# Sheet2.net
KiCad netlist of a schematic drawn in Altium Designer
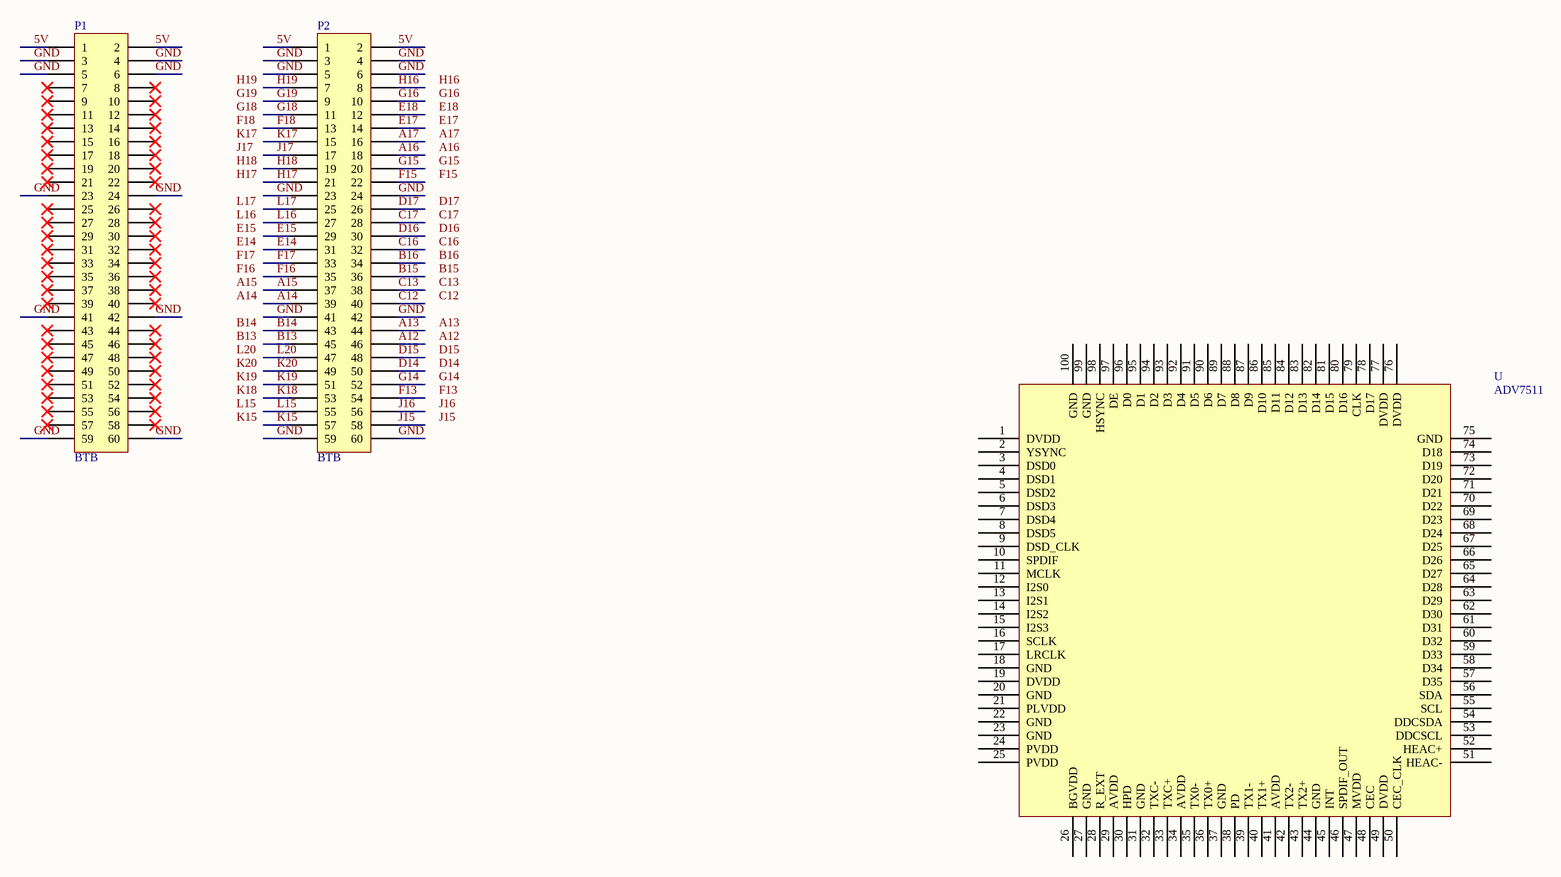
[diagram p0: Sheet2.SchDoc]

(export (version "E")
  (design (tool "Eeschema 10.0.6"))
  (components
    (comp (ref "P1")
      (value "BTB")
      (footprint "BTBCON_0.8mm_60P")
      (description "Header, 30-Pin, Dual row")
      (fields (field (name "PUBLISHER") "Altium Limited"))
      (libsource (lib "Miscellaneous Connectors") (part "Header 30X2"))
    )
    (comp (ref "P2")
      (value "BTB")
      (footprint "BTBCON_0.8mm_60P")
      (description "Header, 30-Pin, Dual row")
      (fields (field (name "PUBLISHER") "Altium Limited"))
      (libsource (lib "Miscellaneous Connectors") (part "Header 30X2"))
    )
    (comp (ref "U") (value "ADV7511") (libsource (lib "ADV7511") (part "ADV7511")))
  )
  (nets
    (net (code "1") (name "/5V") (class "Default")
      (node (ref "P1") (pin "1") (pinfunction "1_1") (pintype "passive"))
      (node (ref "P1") (pin "2") (pinfunction "2_2") (pintype "passive"))
      (node (ref "P2") (pin "1") (pinfunction "1_1") (pintype "passive"))
      (node (ref "P2") (pin "2") (pinfunction "2_2") (pintype "passive"))
    )
    (net (code "2") (name "/A12") (class "Default")
      (node (ref "P2") (pin "46") (pinfunction "46_46") (pintype "passive"))
    )
    (net (code "3") (name "/A13") (class "Default")
      (node (ref "P2") (pin "44") (pinfunction "44_44") (pintype "passive"))
    )
    (net (code "4") (name "/A14") (class "Default")
      (node (ref "P2") (pin "39") (pinfunction "39_39") (pintype "passive"))
    )
    (net (code "5") (name "/A15") (class "Default")
      (node (ref "P2") (pin "37") (pinfunction "37_37") (pintype "passive"))
    )
    (net (code "6") (name "/A16") (class "Default")
      (node (ref "P2") (pin "18") (pinfunction "18_18") (pintype "passive"))
    )
    (net (code "7") (name "/A17") (class "Default")
      (node (ref "P2") (pin "16") (pinfunction "16_16") (pintype "passive"))
    )
    (net (code "8") (name "/B13") (class "Default")
      (node (ref "P2") (pin "45") (pinfunction "45_45") (pintype "passive"))
    )
    (net (code "9") (name "/B14") (class "Default")
      (node (ref "P2") (pin "43") (pinfunction "43_43") (pintype "passive"))
    )
    (net (code "10") (name "/B15") (class "Default")
      (node (ref "P2") (pin "36") (pinfunction "36_36") (pintype "passive"))
    )
    (net (code "11") (name "/B16") (class "Default")
      (node (ref "P2") (pin "34") (pinfunction "34_34") (pintype "passive"))
    )
    (net (code "12") (name "/C12") (class "Default")
      (node (ref "P2") (pin "40") (pinfunction "40_40") (pintype "passive"))
    )
    (net (code "13") (name "/C13") (class "Default")
      (node (ref "P2") (pin "38") (pinfunction "38_38") (pintype "passive"))
    )
    (net (code "14") (name "/C16") (class "Default")
      (node (ref "P2") (pin "32") (pinfunction "32_32") (pintype "passive"))
    )
    (net (code "15") (name "/C17") (class "Default")
      (node (ref "P2") (pin "28") (pinfunction "28_28") (pintype "passive"))
    )
    (net (code "16") (name "/D14") (class "Default")
      (node (ref "P2") (pin "50") (pinfunction "50_50") (pintype "passive"))
    )
    (net (code "17") (name "/D15") (class "Default")
      (node (ref "P2") (pin "48") (pinfunction "48_48") (pintype "passive"))
    )
    (net (code "18") (name "/D16") (class "Default")
      (node (ref "P2") (pin "30") (pinfunction "30_30") (pintype "passive"))
    )
    (net (code "19") (name "/D17") (class "Default")
      (node (ref "P2") (pin "26") (pinfunction "26_26") (pintype "passive"))
    )
    (net (code "20") (name "/E14") (class "Default")
      (node (ref "P2") (pin "31") (pinfunction "31_31") (pintype "passive"))
    )
    (net (code "21") (name "/E15") (class "Default")
      (node (ref "P2") (pin "29") (pinfunction "29_29") (pintype "passive"))
    )
    (net (code "22") (name "/E17") (class "Default")
      (node (ref "P2") (pin "14") (pinfunction "14_14") (pintype "passive"))
    )
    (net (code "23") (name "/E18") (class "Default")
      (node (ref "P2") (pin "12") (pinfunction "12_12") (pintype "passive"))
    )
    (net (code "24") (name "/F13") (class "Default")
      (node (ref "P2") (pin "54") (pinfunction "54_54") (pintype "passive"))
    )
    (net (code "25") (name "/F15") (class "Default")
      (node (ref "P2") (pin "22") (pinfunction "22_22") (pintype "passive"))
    )
    (net (code "26") (name "/F16") (class "Default")
      (node (ref "P2") (pin "35") (pinfunction "35_35") (pintype "passive"))
    )
    (net (code "27") (name "/F17") (class "Default")
      (node (ref "P2") (pin "33") (pinfunction "33_33") (pintype "passive"))
    )
    (net (code "28") (name "/F18") (class "Default")
      (node (ref "P2") (pin "13") (pinfunction "13_13") (pintype "passive"))
    )
    (net (code "29") (name "/G14") (class "Default")
      (node (ref "P2") (pin "52") (pinfunction "52_52") (pintype "passive"))
    )
    (net (code "30") (name "/G15") (class "Default")
      (node (ref "P2") (pin "20") (pinfunction "20_20") (pintype "passive"))
    )
    (net (code "31") (name "/G16") (class "Default")
      (node (ref "P2") (pin "10") (pinfunction "10_10") (pintype "passive"))
    )
    (net (code "32") (name "/G18") (class "Default")
      (node (ref "P2") (pin "11") (pinfunction "11_11") (pintype "passive"))
    )
    (net (code "33") (name "/G19") (class "Default")
      (node (ref "P2") (pin "9") (pinfunction "9_9") (pintype "passive"))
    )
    (net (code "34") (name "/GND") (class "Default")
      (node (ref "P1") (pin "23") (pinfunction "23_23") (pintype "passive"))
      (node (ref "P1") (pin "24") (pinfunction "24_24") (pintype "passive"))
      (node (ref "P1") (pin "3") (pinfunction "3_3") (pintype "passive"))
      (node (ref "P1") (pin "4") (pinfunction "4_4") (pintype "passive"))
      (node (ref "P1") (pin "41") (pinfunction "41_41") (pintype "passive"))
      (node (ref "P1") (pin "42") (pinfunction "42_42") (pintype "passive"))
      (node (ref "P1") (pin "5") (pinfunction "5_5") (pintype "passive"))
      (node (ref "P1") (pin "59") (pinfunction "59_59") (pintype "passive"))
      (node (ref "P1") (pin "6") (pinfunction "6_6") (pintype "passive"))
      (node (ref "P1") (pin "60") (pinfunction "60_60") (pintype "passive"))
      (node (ref "P2") (pin "23") (pinfunction "23_23") (pintype "passive"))
      (node (ref "P2") (pin "24") (pinfunction "24_24") (pintype "passive"))
      (node (ref "P2") (pin "3") (pinfunction "3_3") (pintype "passive"))
      (node (ref "P2") (pin "4") (pinfunction "4_4") (pintype "passive"))
      (node (ref "P2") (pin "41") (pinfunction "41_41") (pintype "passive"))
      (node (ref "P2") (pin "42") (pinfunction "42_42") (pintype "passive"))
      (node (ref "P2") (pin "5") (pinfunction "5_5") (pintype "passive"))
      (node (ref "P2") (pin "59") (pinfunction "59_59") (pintype "passive"))
      (node (ref "P2") (pin "6") (pinfunction "6_6") (pintype "passive"))
      (node (ref "P2") (pin "60") (pinfunction "60_60") (pintype "passive"))
    )
    (net (code "35") (name "/H16") (class "Default")
      (node (ref "P2") (pin "8") (pinfunction "8_8") (pintype "passive"))
    )
    (net (code "36") (name "/H17") (class "Default")
      (node (ref "P2") (pin "21") (pinfunction "21_21") (pintype "passive"))
    )
    (net (code "37") (name "/H18") (class "Default")
      (node (ref "P2") (pin "19") (pinfunction "19_19") (pintype "passive"))
    )
    (net (code "38") (name "/H19") (class "Default")
      (node (ref "P2") (pin "7") (pinfunction "7_7") (pintype "passive"))
    )
    (net (code "39") (name "/J15") (class "Default")
      (node (ref "P2") (pin "58") (pinfunction "58_58") (pintype "passive"))
    )
    (net (code "40") (name "/J16") (class "Default")
      (node (ref "P2") (pin "56") (pinfunction "56_56") (pintype "passive"))
    )
    (net (code "41") (name "/J17") (class "Default")
      (node (ref "P2") (pin "17") (pinfunction "17_17") (pintype "passive"))
    )
    (net (code "42") (name "/K15") (class "Default")
      (node (ref "P2") (pin "57") (pinfunction "57_57") (pintype "passive"))
    )
    (net (code "43") (name "/K17") (class "Default")
      (node (ref "P2") (pin "15") (pinfunction "15_15") (pintype "passive"))
    )
    (net (code "44") (name "/K18") (class "Default")
      (node (ref "P2") (pin "53") (pinfunction "53_53") (pintype "passive"))
    )
    (net (code "45") (name "/K19") (class "Default")
      (node (ref "P2") (pin "51") (pinfunction "51_51") (pintype "passive"))
    )
    (net (code "46") (name "/K20") (class "Default")
      (node (ref "P2") (pin "49") (pinfunction "49_49") (pintype "passive"))
    )
    (net (code "47") (name "/L15") (class "Default")
      (node (ref "P2") (pin "55") (pinfunction "55_55") (pintype "passive"))
    )
    (net (code "48") (name "/L16") (class "Default")
      (node (ref "P2") (pin "27") (pinfunction "27_27") (pintype "passive"))
    )
    (net (code "49") (name "/L17") (class "Default")
      (node (ref "P2") (pin "25") (pinfunction "25_25") (pintype "passive"))
    )
    (net (code "50") (name "/L20") (class "Default")
      (node (ref "P2") (pin "47") (pinfunction "47_47") (pintype "passive"))
    )
    (net (code "51") (name "unconnected-(P1-Pad7)") (class "Default")
      (node (ref "P1") (pin "7") (pinfunction "7_7") (pintype "passive+no_connect"))
    )
    (net (code "52") (name "unconnected-(P1-Pad8)") (class "Default")
      (node (ref "P1") (pin "8") (pinfunction "8_8") (pintype "passive+no_connect"))
    )
    (net (code "53") (name "unconnected-(P1-Pad9)") (class "Default")
      (node (ref "P1") (pin "9") (pinfunction "9_9") (pintype "passive+no_connect"))
    )
    (net (code "54") (name "unconnected-(P1-Pad10)") (class "Default")
      (node (ref "P1") (pin "10") (pinfunction "10_10") (pintype "passive+no_connect"))
    )
    (net (code "55") (name "unconnected-(P1-Pad11)") (class "Default")
      (node (ref "P1") (pin "11") (pinfunction "11_11") (pintype "passive+no_connect"))
    )
    (net (code "56") (name "unconnected-(P1-Pad12)") (class "Default")
      (node (ref "P1") (pin "12") (pinfunction "12_12") (pintype "passive+no_connect"))
    )
    (net (code "57") (name "unconnected-(P1-Pad13)") (class "Default")
      (node (ref "P1") (pin "13") (pinfunction "13_13") (pintype "passive+no_connect"))
    )
    (net (code "58") (name "unconnected-(P1-Pad14)") (class "Default")
      (node (ref "P1") (pin "14") (pinfunction "14_14") (pintype "passive+no_connect"))
    )
    (net (code "59") (name "unconnected-(P1-Pad15)") (class "Default")
      (node (ref "P1") (pin "15") (pinfunction "15_15") (pintype "passive+no_connect"))
    )
    (net (code "60") (name "unconnected-(P1-Pad16)") (class "Default")
      (node (ref "P1") (pin "16") (pinfunction "16_16") (pintype "passive+no_connect"))
    )
    (net (code "61") (name "unconnected-(P1-Pad17)") (class "Default")
      (node (ref "P1") (pin "17") (pinfunction "17_17") (pintype "passive+no_connect"))
    )
    (net (code "62") (name "unconnected-(P1-Pad18)") (class "Default")
      (node (ref "P1") (pin "18") (pinfunction "18_18") (pintype "passive+no_connect"))
    )
    (net (code "63") (name "unconnected-(P1-Pad19)") (class "Default")
      (node (ref "P1") (pin "19") (pinfunction "19_19") (pintype "passive+no_connect"))
    )
    (net (code "64") (name "unconnected-(P1-Pad20)") (class "Default")
      (node (ref "P1") (pin "20") (pinfunction "20_20") (pintype "passive+no_connect"))
    )
    (net (code "65") (name "unconnected-(P1-Pad21)") (class "Default")
      (node (ref "P1") (pin "21") (pinfunction "21_21") (pintype "passive+no_connect"))
    )
    (net (code "66") (name "unconnected-(P1-Pad22)") (class "Default")
      (node (ref "P1") (pin "22") (pinfunction "22_22") (pintype "passive+no_connect"))
    )
    (net (code "67") (name "unconnected-(P1-Pad25)") (class "Default")
      (node (ref "P1") (pin "25") (pinfunction "25_25") (pintype "passive+no_connect"))
    )
    (net (code "68") (name "unconnected-(P1-Pad26)") (class "Default")
      (node (ref "P1") (pin "26") (pinfunction "26_26") (pintype "passive+no_connect"))
    )
    (net (code "69") (name "unconnected-(P1-Pad27)") (class "Default")
      (node (ref "P1") (pin "27") (pinfunction "27_27") (pintype "passive+no_connect"))
    )
    (net (code "70") (name "unconnected-(P1-Pad28)") (class "Default")
      (node (ref "P1") (pin "28") (pinfunction "28_28") (pintype "passive+no_connect"))
    )
    (net (code "71") (name "unconnected-(P1-Pad29)") (class "Default")
      (node (ref "P1") (pin "29") (pinfunction "29_29") (pintype "passive+no_connect"))
    )
    (net (code "72") (name "unconnected-(P1-Pad30)") (class "Default")
      (node (ref "P1") (pin "30") (pinfunction "30_30") (pintype "passive+no_connect"))
    )
    (net (code "73") (name "unconnected-(P1-Pad31)") (class "Default")
      (node (ref "P1") (pin "31") (pinfunction "31_31") (pintype "passive+no_connect"))
    )
    (net (code "74") (name "unconnected-(P1-Pad32)") (class "Default")
      (node (ref "P1") (pin "32") (pinfunction "32_32") (pintype "passive+no_connect"))
    )
    (net (code "75") (name "unconnected-(P1-Pad33)") (class "Default")
      (node (ref "P1") (pin "33") (pinfunction "33_33") (pintype "passive+no_connect"))
    )
    (net (code "76") (name "unconnected-(P1-Pad34)") (class "Default")
      (node (ref "P1") (pin "34") (pinfunction "34_34") (pintype "passive+no_connect"))
    )
    (net (code "77") (name "unconnected-(P1-Pad35)") (class "Default")
      (node (ref "P1") (pin "35") (pinfunction "35_35") (pintype "passive+no_connect"))
    )
    (net (code "78") (name "unconnected-(P1-Pad36)") (class "Default")
      (node (ref "P1") (pin "36") (pinfunction "36_36") (pintype "passive+no_connect"))
    )
    (net (code "79") (name "unconnected-(P1-Pad37)") (class "Default")
      (node (ref "P1") (pin "37") (pinfunction "37_37") (pintype "passive+no_connect"))
    )
    (net (code "80") (name "unconnected-(P1-Pad38)") (class "Default")
      (node (ref "P1") (pin "38") (pinfunction "38_38") (pintype "passive+no_connect"))
    )
    (net (code "81") (name "unconnected-(P1-Pad39)") (class "Default")
      (node (ref "P1") (pin "39") (pinfunction "39_39") (pintype "passive+no_connect"))
    )
    (net (code "82") (name "unconnected-(P1-Pad40)") (class "Default")
      (node (ref "P1") (pin "40") (pinfunction "40_40") (pintype "passive+no_connect"))
    )
    (net (code "83") (name "unconnected-(P1-Pad43)") (class "Default")
      (node (ref "P1") (pin "43") (pinfunction "43_43") (pintype "passive+no_connect"))
    )
    (net (code "84") (name "unconnected-(P1-Pad44)") (class "Default")
      (node (ref "P1") (pin "44") (pinfunction "44_44") (pintype "passive+no_connect"))
    )
    (net (code "85") (name "unconnected-(P1-Pad45)") (class "Default")
      (node (ref "P1") (pin "45") (pinfunction "45_45") (pintype "passive+no_connect"))
    )
    (net (code "86") (name "unconnected-(P1-Pad46)") (class "Default")
      (node (ref "P1") (pin "46") (pinfunction "46_46") (pintype "passive+no_connect"))
    )
    (net (code "87") (name "unconnected-(P1-Pad47)") (class "Default")
      (node (ref "P1") (pin "47") (pinfunction "47_47") (pintype "passive+no_connect"))
    )
    (net (code "88") (name "unconnected-(P1-Pad48)") (class "Default")
      (node (ref "P1") (pin "48") (pinfunction "48_48") (pintype "passive+no_connect"))
    )
    (net (code "89") (name "unconnected-(P1-Pad49)") (class "Default")
      (node (ref "P1") (pin "49") (pinfunction "49_49") (pintype "passive+no_connect"))
    )
    (net (code "90") (name "unconnected-(P1-Pad50)") (class "Default")
      (node (ref "P1") (pin "50") (pinfunction "50_50") (pintype "passive+no_connect"))
    )
    (net (code "91") (name "unconnected-(P1-Pad51)") (class "Default")
      (node (ref "P1") (pin "51") (pinfunction "51_51") (pintype "passive+no_connect"))
    )
    (net (code "92") (name "unconnected-(P1-Pad52)") (class "Default")
      (node (ref "P1") (pin "52") (pinfunction "52_52") (pintype "passive+no_connect"))
    )
    (net (code "93") (name "unconnected-(P1-Pad53)") (class "Default")
      (node (ref "P1") (pin "53") (pinfunction "53_53") (pintype "passive+no_connect"))
    )
    (net (code "94") (name "unconnected-(P1-Pad54)") (class "Default")
      (node (ref "P1") (pin "54") (pinfunction "54_54") (pintype "passive+no_connect"))
    )
    (net (code "95") (name "unconnected-(P1-Pad55)") (class "Default")
      (node (ref "P1") (pin "55") (pinfunction "55_55") (pintype "passive+no_connect"))
    )
    (net (code "96") (name "unconnected-(P1-Pad56)") (class "Default")
      (node (ref "P1") (pin "56") (pinfunction "56_56") (pintype "passive+no_connect"))
    )
    (net (code "97") (name "unconnected-(P1-Pad57)") (class "Default")
      (node (ref "P1") (pin "57") (pinfunction "57_57") (pintype "passive+no_connect"))
    )
    (net (code "98") (name "unconnected-(P1-Pad58)") (class "Default")
      (node (ref "P1") (pin "58") (pinfunction "58_58") (pintype "passive+no_connect"))
    )
    (net (code "99") (name "unconnected-(U-AVDD-Pad29)") (class "Default")
      (node (ref "U") (pin "29") (pinfunction "AVDD_29") (pintype "passive"))
    )
    (net (code "100") (name "unconnected-(U-AVDD-Pad34)") (class "Default")
      (node (ref "U") (pin "34") (pinfunction "AVDD_34") (pintype "passive"))
    )
    (net (code "101") (name "unconnected-(U-AVDD-Pad41)") (class "Default")
      (node (ref "U") (pin "41") (pinfunction "AVDD_41") (pintype "passive"))
    )
    (net (code "102") (name "unconnected-(U-BGVDD-Pad26)") (class "Default")
      (node (ref "U") (pin "26") (pinfunction "BGVDD_26") (pintype "passive"))
    )
    (net (code "103") (name "unconnected-(U-CEC-Pad48)") (class "Default")
      (node (ref "U") (pin "48") (pinfunction "CEC_48") (pintype "passive"))
    )
    (net (code "104") (name "unconnected-(U-CEC_CLK-Pad50)") (class "Default")
      (node (ref "U") (pin "50") (pinfunction "CEC_CLK_50") (pintype "passive"))
    )
    (net (code "105") (name "unconnected-(U-CLK-Pad79)") (class "Default")
      (node (ref "U") (pin "79") (pinfunction "CLK_79") (pintype "passive"))
    )
    (net (code "106") (name "unconnected-(U-D0-Pad96)") (class "Default")
      (node (ref "U") (pin "96") (pinfunction "D0_96") (pintype "passive"))
    )
    (net (code "107") (name "unconnected-(U-D1-Pad95)") (class "Default")
      (node (ref "U") (pin "95") (pinfunction "D1_95") (pintype "passive"))
    )
    (net (code "108") (name "unconnected-(U-D2-Pad94)") (class "Default")
      (node (ref "U") (pin "94") (pinfunction "D2_94") (pintype "passive"))
    )
    (net (code "109") (name "unconnected-(U-D3-Pad93)") (class "Default")
      (node (ref "U") (pin "93") (pinfunction "D3_93") (pintype "passive"))
    )
    (net (code "110") (name "unconnected-(U-D4-Pad92)") (class "Default")
      (node (ref "U") (pin "92") (pinfunction "D4_92") (pintype "passive"))
    )
    (net (code "111") (name "unconnected-(U-D5-Pad91)") (class "Default")
      (node (ref "U") (pin "91") (pinfunction "D5_91") (pintype "passive"))
    )
    (net (code "112") (name "unconnected-(U-D6-Pad90)") (class "Default")
      (node (ref "U") (pin "90") (pinfunction "D6_90") (pintype "passive"))
    )
    (net (code "113") (name "unconnected-(U-D7-Pad89)") (class "Default")
      (node (ref "U") (pin "89") (pinfunction "D7_89") (pintype "passive"))
    )
    (net (code "114") (name "unconnected-(U-D8-Pad88)") (class "Default")
      (node (ref "U") (pin "88") (pinfunction "D8_88") (pintype "passive"))
    )
    (net (code "115") (name "unconnected-(U-D9-Pad87)") (class "Default")
      (node (ref "U") (pin "87") (pinfunction "D9_87") (pintype "passive"))
    )
    (net (code "116") (name "unconnected-(U-D10-Pad86)") (class "Default")
      (node (ref "U") (pin "86") (pinfunction "D10_86") (pintype "passive"))
    )
    (net (code "117") (name "unconnected-(U-D11-Pad85)") (class "Default")
      (node (ref "U") (pin "85") (pinfunction "D11_85") (pintype "passive"))
    )
    (net (code "118") (name "unconnected-(U-D12-Pad84)") (class "Default")
      (node (ref "U") (pin "84") (pinfunction "D12_84") (pintype "passive"))
    )
    (net (code "119") (name "unconnected-(U-D13-Pad83)") (class "Default")
      (node (ref "U") (pin "83") (pinfunction "D13_83") (pintype "passive"))
    )
    (net (code "120") (name "unconnected-(U-D14-Pad82)") (class "Default")
      (node (ref "U") (pin "82") (pinfunction "D14_82") (pintype "passive"))
    )
    (net (code "121") (name "unconnected-(U-D15-Pad81)") (class "Default")
      (node (ref "U") (pin "81") (pinfunction "D15_81") (pintype "passive"))
    )
    (net (code "122") (name "unconnected-(U-D16-Pad80)") (class "Default")
      (node (ref "U") (pin "80") (pinfunction "D16_80") (pintype "passive"))
    )
    (net (code "123") (name "unconnected-(U-D17-Pad78)") (class "Default")
      (node (ref "U") (pin "78") (pinfunction "D17_78") (pintype "passive"))
    )
    (net (code "124") (name "unconnected-(U-D18-Pad74)") (class "Default")
      (node (ref "U") (pin "74") (pinfunction "D18_74") (pintype "passive"))
    )
    (net (code "125") (name "unconnected-(U-D19-Pad73)") (class "Default")
      (node (ref "U") (pin "73") (pinfunction "D19_73") (pintype "passive"))
    )
    (net (code "126") (name "unconnected-(U-D20-Pad72)") (class "Default")
      (node (ref "U") (pin "72") (pinfunction "D20_72") (pintype "passive"))
    )
    (net (code "127") (name "unconnected-(U-D21-Pad71)") (class "Default")
      (node (ref "U") (pin "71") (pinfunction "D21_71") (pintype "passive"))
    )
    (net (code "128") (name "unconnected-(U-D22-Pad70)") (class "Default")
      (node (ref "U") (pin "70") (pinfunction "D22_70") (pintype "passive"))
    )
    (net (code "129") (name "unconnected-(U-D23-Pad69)") (class "Default")
      (node (ref "U") (pin "69") (pinfunction "D23_69") (pintype "passive"))
    )
    (net (code "130") (name "unconnected-(U-D24-Pad68)") (class "Default")
      (node (ref "U") (pin "68") (pinfunction "D24_68") (pintype "passive"))
    )
    (net (code "131") (name "unconnected-(U-D25-Pad67)") (class "Default")
      (node (ref "U") (pin "67") (pinfunction "D25_67") (pintype "passive"))
    )
    (net (code "132") (name "unconnected-(U-D26-Pad66)") (class "Default")
      (node (ref "U") (pin "66") (pinfunction "D26_66") (pintype "passive"))
    )
    (net (code "133") (name "unconnected-(U-D27-Pad65)") (class "Default")
      (node (ref "U") (pin "65") (pinfunction "D27_65") (pintype "passive"))
    )
    (net (code "134") (name "unconnected-(U-D28-Pad64)") (class "Default")
      (node (ref "U") (pin "64") (pinfunction "D28_64") (pintype "passive"))
    )
    (net (code "135") (name "unconnected-(U-D29-Pad63)") (class "Default")
      (node (ref "U") (pin "63") (pinfunction "D29_63") (pintype "passive"))
    )
    (net (code "136") (name "unconnected-(U-D30-Pad62)") (class "Default")
      (node (ref "U") (pin "62") (pinfunction "D30_62") (pintype "passive"))
    )
    (net (code "137") (name "unconnected-(U-D31-Pad61)") (class "Default")
      (node (ref "U") (pin "61") (pinfunction "D31_61") (pintype "passive"))
    )
    (net (code "138") (name "unconnected-(U-D32-Pad60)") (class "Default")
      (node (ref "U") (pin "60") (pinfunction "D32_60") (pintype "passive"))
    )
    (net (code "139") (name "unconnected-(U-D33-Pad59)") (class "Default")
      (node (ref "U") (pin "59") (pinfunction "D33_59") (pintype "passive"))
    )
    (net (code "140") (name "unconnected-(U-D34-Pad58)") (class "Default")
      (node (ref "U") (pin "58") (pinfunction "D34_58") (pintype "passive"))
    )
    (net (code "141") (name "unconnected-(U-D35-Pad57)") (class "Default")
      (node (ref "U") (pin "57") (pinfunction "D35_57") (pintype "passive"))
    )
    (net (code "142") (name "unconnected-(U-DDCSCL-Pad53)") (class "Default")
      (node (ref "U") (pin "53") (pinfunction "DDCSCL_53") (pintype "passive"))
    )
    (net (code "143") (name "unconnected-(U-DDCSDA-Pad54)") (class "Default")
      (node (ref "U") (pin "54") (pinfunction "DDCSDA_54") (pintype "passive"))
    )
    (net (code "144") (name "unconnected-(U-DE-Pad97)") (class "Default")
      (node (ref "U") (pin "97") (pinfunction "DE_97") (pintype "passive"))
    )
    (net (code "145") (name "unconnected-(U-DSD0-Pad3)") (class "Default")
      (node (ref "U") (pin "3") (pinfunction "DSD0_3") (pintype "passive"))
    )
    (net (code "146") (name "unconnected-(U-DSD1-Pad4)") (class "Default")
      (node (ref "U") (pin "4") (pinfunction "DSD1_4") (pintype "passive"))
    )
    (net (code "147") (name "unconnected-(U-DSD2-Pad5)") (class "Default")
      (node (ref "U") (pin "5") (pinfunction "DSD2_5") (pintype "passive"))
    )
    (net (code "148") (name "unconnected-(U-DSD3-Pad6)") (class "Default")
      (node (ref "U") (pin "6") (pinfunction "DSD3_6") (pintype "passive"))
    )
    (net (code "149") (name "unconnected-(U-DSD4-Pad7)") (class "Default")
      (node (ref "U") (pin "7") (pinfunction "DSD4_7") (pintype "passive"))
    )
    (net (code "150") (name "unconnected-(U-DSD5-Pad8)") (class "Default")
      (node (ref "U") (pin "8") (pinfunction "DSD5_8") (pintype "passive"))
    )
    (net (code "151") (name "unconnected-(U-DSD_CLK-Pad9)") (class "Default")
      (node (ref "U") (pin "9") (pinfunction "DSD_CLK_9") (pintype "passive"))
    )
    (net (code "152") (name "unconnected-(U-DVDD-Pad1)") (class "Default")
      (node (ref "U") (pin "1") (pinfunction "DVDD_1") (pintype "passive"))
    )
    (net (code "153") (name "unconnected-(U-DVDD-Pad19)") (class "Default")
      (node (ref "U") (pin "19") (pinfunction "DVDD_19") (pintype "passive"))
    )
    (net (code "154") (name "unconnected-(U-DVDD-Pad49)") (class "Default")
      (node (ref "U") (pin "49") (pinfunction "DVDD_49") (pintype "passive"))
    )
    (net (code "155") (name "unconnected-(U-DVDD-Pad76)") (class "Default")
      (node (ref "U") (pin "76") (pinfunction "DVDD_76") (pintype "passive"))
    )
    (net (code "156") (name "unconnected-(U-DVDD-Pad77)") (class "Default")
      (node (ref "U") (pin "77") (pinfunction "DVDD_77") (pintype "passive"))
    )
    (net (code "157") (name "unconnected-(U-GND-Pad18)") (class "Default")
      (node (ref "U") (pin "18") (pinfunction "GND_18") (pintype "passive"))
    )
    (net (code "158") (name "unconnected-(U-GND-Pad20)") (class "Default")
      (node (ref "U") (pin "20") (pinfunction "GND_20") (pintype "passive"))
    )
    (net (code "159") (name "unconnected-(U-GND-Pad22)") (class "Default")
      (node (ref "U") (pin "22") (pinfunction "GND_22") (pintype "passive"))
    )
    (net (code "160") (name "unconnected-(U-GND-Pad23)") (class "Default")
      (node (ref "U") (pin "23") (pinfunction "GND_23") (pintype "passive"))
    )
    (net (code "161") (name "unconnected-(U-GND-Pad27)") (class "Default")
      (node (ref "U") (pin "27") (pinfunction "GND_27") (pintype "passive"))
    )
    (net (code "162") (name "unconnected-(U-GND-Pad31)") (class "Default")
      (node (ref "U") (pin "31") (pinfunction "GND_31") (pintype "passive"))
    )
    (net (code "163") (name "unconnected-(U-GND-Pad37)") (class "Default")
      (node (ref "U") (pin "37") (pinfunction "GND_37") (pintype "passive"))
    )
    (net (code "164") (name "unconnected-(U-GND-Pad44)") (class "Default")
      (node (ref "U") (pin "44") (pinfunction "GND_44") (pintype "passive"))
    )
    (net (code "165") (name "unconnected-(U-GND-Pad75)") (class "Default")
      (node (ref "U") (pin "75") (pinfunction "GND_75") (pintype "passive"))
    )
    (net (code "166") (name "unconnected-(U-GND-Pad99)") (class "Default")
      (node (ref "U") (pin "99") (pinfunction "GND_99") (pintype "passive"))
    )
    (net (code "167") (name "unconnected-(U-GND-Pad100)") (class "Default")
      (node (ref "U") (pin "100") (pinfunction "GND_100") (pintype "passive"))
    )
    (net (code "168") (name "unconnected-(U-HEAC+-Pad52)") (class "Default")
      (node (ref "U") (pin "52") (pinfunction "HEAC+_52") (pintype "passive"))
    )
    (net (code "169") (name "unconnected-(U-HEAC--Pad51)") (class "Default")
      (node (ref "U") (pin "51") (pinfunction "HEAC-_51") (pintype "passive"))
    )
    (net (code "170") (name "unconnected-(U-HPD-Pad30)") (class "Default")
      (node (ref "U") (pin "30") (pinfunction "HPD_30") (pintype "passive"))
    )
    (net (code "171") (name "unconnected-(U-HSYNC-Pad98)") (class "Default")
      (node (ref "U") (pin "98") (pinfunction "HSYNC_98") (pintype "passive"))
    )
    (net (code "172") (name "unconnected-(U-I2S0-Pad12)") (class "Default")
      (node (ref "U") (pin "12") (pinfunction "I2S0_12") (pintype "passive"))
    )
    (net (code "173") (name "unconnected-(U-I2S1-Pad13)") (class "Default")
      (node (ref "U") (pin "13") (pinfunction "I2S1_13") (pintype "passive"))
    )
    (net (code "174") (name "unconnected-(U-I2S2-Pad14)") (class "Default")
      (node (ref "U") (pin "14") (pinfunction "I2S2_14") (pintype "passive"))
    )
    (net (code "175") (name "unconnected-(U-I2S3-Pad15)") (class "Default")
      (node (ref "U") (pin "15") (pinfunction "I2S3_15") (pintype "passive"))
    )
    (net (code "176") (name "unconnected-(U-INT-Pad45)") (class "Default")
      (node (ref "U") (pin "45") (pinfunction "INT_45") (pintype "passive"))
    )
    (net (code "177") (name "unconnected-(U-LRCLK-Pad17)") (class "Default")
      (node (ref "U") (pin "17") (pinfunction "LRCLK_17") (pintype "passive"))
    )
    (net (code "178") (name "unconnected-(U-MCLK-Pad11)") (class "Default")
      (node (ref "U") (pin "11") (pinfunction "MCLK_11") (pintype "passive"))
    )
    (net (code "179") (name "unconnected-(U-MVDD-Pad47)") (class "Default")
      (node (ref "U") (pin "47") (pinfunction "MVDD_47") (pintype "passive"))
    )
    (net (code "180") (name "unconnected-(U-PD-Pad38)") (class "Default")
      (node (ref "U") (pin "38") (pinfunction "PD_38") (pintype "passive"))
    )
    (net (code "181") (name "unconnected-(U-PLVDD-Pad21)") (class "Default")
      (node (ref "U") (pin "21") (pinfunction "PLVDD_21") (pintype "passive"))
    )
    (net (code "182") (name "unconnected-(U-PVDD-Pad24)") (class "Default")
      (node (ref "U") (pin "24") (pinfunction "PVDD_24") (pintype "passive"))
    )
    (net (code "183") (name "unconnected-(U-PVDD-Pad25)") (class "Default")
      (node (ref "U") (pin "25") (pinfunction "PVDD_25") (pintype "passive"))
    )
    (net (code "184") (name "unconnected-(U-R_EXT-Pad28)") (class "Default")
      (node (ref "U") (pin "28") (pinfunction "R_EXT_28") (pintype "passive"))
    )
    (net (code "185") (name "unconnected-(U-SCL-Pad55)") (class "Default")
      (node (ref "U") (pin "55") (pinfunction "SCL_55") (pintype "passive"))
    )
    (net (code "186") (name "unconnected-(U-SCLK-Pad16)") (class "Default")
      (node (ref "U") (pin "16") (pinfunction "SCLK_16") (pintype "passive"))
    )
    (net (code "187") (name "unconnected-(U-SDA-Pad56)") (class "Default")
      (node (ref "U") (pin "56") (pinfunction "SDA_56") (pintype "passive"))
    )
    (net (code "188") (name "unconnected-(U-SPDIF-Pad10)") (class "Default")
      (node (ref "U") (pin "10") (pinfunction "SPDIF_10") (pintype "passive"))
    )
    (net (code "189") (name "unconnected-(U-SPDIF_OUT-Pad46)") (class "Default")
      (node (ref "U") (pin "46") (pinfunction "SPDIF_OUT_46") (pintype "passive"))
    )
    (net (code "190") (name "unconnected-(U-TX0+-Pad36)") (class "Default")
      (node (ref "U") (pin "36") (pinfunction "TX0+_36") (pintype "passive"))
    )
    (net (code "191") (name "unconnected-(U-TX0--Pad35)") (class "Default")
      (node (ref "U") (pin "35") (pinfunction "TX0-_35") (pintype "passive"))
    )
    (net (code "192") (name "unconnected-(U-TX1+-Pad40)") (class "Default")
      (node (ref "U") (pin "40") (pinfunction "TX1+_40") (pintype "passive"))
    )
    (net (code "193") (name "unconnected-(U-TX1--Pad39)") (class "Default")
      (node (ref "U") (pin "39") (pinfunction "TX1-_39") (pintype "passive"))
    )
    (net (code "194") (name "unconnected-(U-TX2+-Pad43)") (class "Default")
      (node (ref "U") (pin "43") (pinfunction "TX2+_43") (pintype "passive"))
    )
    (net (code "195") (name "unconnected-(U-TX2--Pad42)") (class "Default")
      (node (ref "U") (pin "42") (pinfunction "TX2-_42") (pintype "passive"))
    )
    (net (code "196") (name "unconnected-(U-TXC+-Pad33)") (class "Default")
      (node (ref "U") (pin "33") (pinfunction "TXC+_33") (pintype "passive"))
    )
    (net (code "197") (name "unconnected-(U-TXC--Pad32)") (class "Default")
      (node (ref "U") (pin "32") (pinfunction "TXC-_32") (pintype "passive"))
    )
    (net (code "198") (name "unconnected-(U-YSYNC-Pad2)") (class "Default")
      (node (ref "U") (pin "2") (pinfunction "YSYNC_2") (pintype "passive"))
    )
  )
)
